# LED_Project.net
KiCad netlist of a schematic drawn in EAGLE
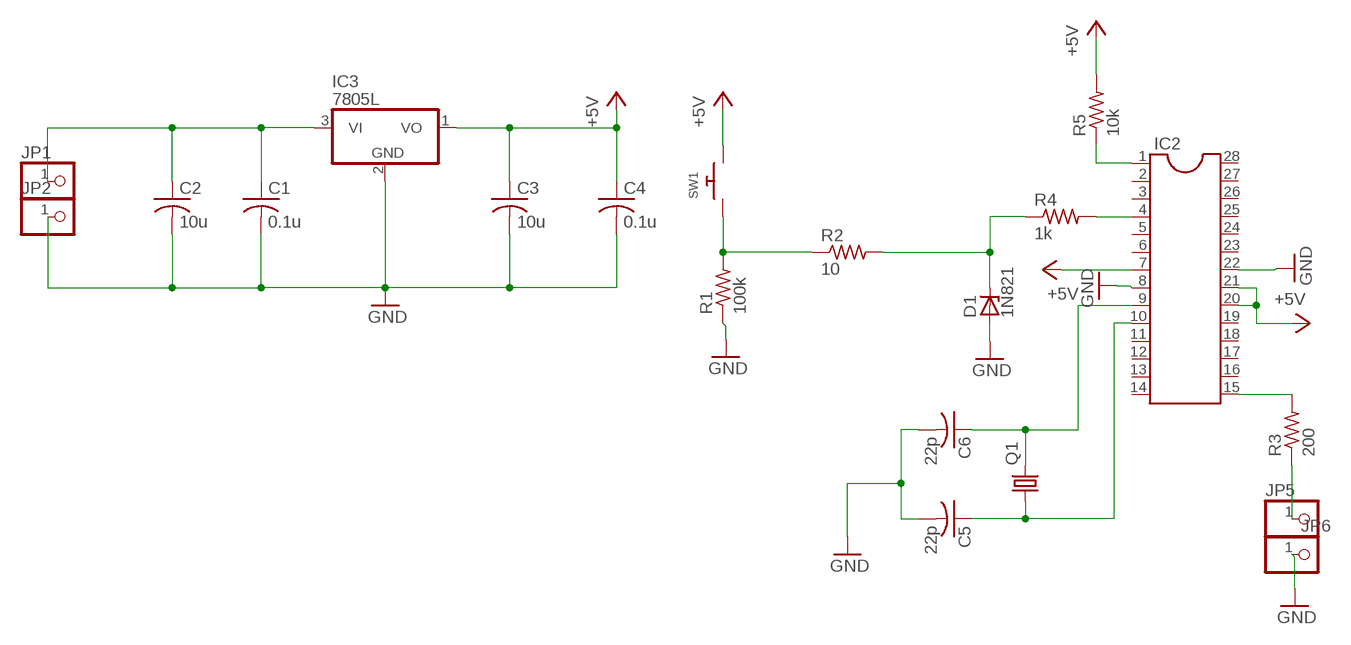
[diagram p0: schematic, sheet 1]

(export (version "E")
  (design (tool "Eeschema 10.0.6"))
  (components
    (comp (ref "C1")
      (value "0.1u")
      (footprint "eagle-import:C0805K")
      (libsource (lib "eagle-import") (part "C-USC0805K"))
    )
    (comp (ref "C2")
      (value "10u")
      (footprint "eagle-import:C0805K")
      (libsource (lib "eagle-import") (part "C-USC0805K"))
    )
    (comp (ref "C3")
      (value "10u")
      (footprint "eagle-import:C0805K")
      (libsource (lib "eagle-import") (part "C-USC0805K"))
    )
    (comp (ref "C4")
      (value "0.1u")
      (footprint "eagle-import:C0805K")
      (libsource (lib "eagle-import") (part "C-USC0805K"))
    )
    (comp (ref "C5")
      (value "22p")
      (footprint "eagle-import:C0805K")
      (libsource (lib "eagle-import") (part "C-USC0805K"))
    )
    (comp (ref "C6")
      (value "22p")
      (footprint "eagle-import:C0805K")
      (libsource (lib "eagle-import") (part "C-USC0805K"))
    )
    (comp (ref "D1")
      (value "1N821")
      (footprint "eagle-import:DO35Z10")
      (libsource (lib "eagle-import") (part "1N821"))
    )
    (comp (ref "IC2")
      (value "DIL28-3")
      (footprint "eagle-import:DIL28-3")
      (libsource (lib "eagle-import") (part "DIL28-3"))
    )
    (comp (ref "IC3")
      (value "7805L")
      (footprint "eagle-import:TO92")
      (libsource (lib "eagle-import") (part "78L05"))
    )
    (comp (ref "JP1")
      (value "PINHD-1X1")
      (footprint "eagle-import:1X01")
      (libsource (lib "eagle-import") (part "PINHD-1X1"))
    )
    (comp (ref "JP2")
      (value "PINHD-1X1")
      (footprint "eagle-import:1X01")
      (libsource (lib "eagle-import") (part "PINHD-1X1"))
    )
    (comp (ref "JP5")
      (value "PINHD-1X1")
      (footprint "eagle-import:1X01")
      (libsource (lib "eagle-import") (part "PINHD-1X1"))
    )
    (comp (ref "JP6")
      (value "PINHD-1X1")
      (footprint "eagle-import:1X01")
      (libsource (lib "eagle-import") (part "PINHD-1X1"))
    )
    (comp (ref "Q1")
      (value "CRYSTALHC49S")
      (footprint "eagle-import:HC49_S")
      (libsource (lib "eagle-import") (part "CRYSTALHC49S"))
    )
    (comp (ref "R1")
      (value "100k")
      (footprint "eagle-import:R0805")
      (libsource (lib "eagle-import") (part "R-US_R0805"))
    )
    (comp (ref "R2")
      (value "10")
      (footprint "eagle-import:R0805")
      (libsource (lib "eagle-import") (part "R-US_R0805"))
    )
    (comp (ref "R3")
      (value "200")
      (footprint "eagle-import:R0805")
      (libsource (lib "eagle-import") (part "R-US_R0805"))
    )
    (comp (ref "R4")
      (value "1k")
      (footprint "eagle-import:R0805")
      (libsource (lib "eagle-import") (part "R-US_R0805"))
    )
    (comp (ref "R5")
      (value "10k")
      (footprint "eagle-import:R0805")
      (libsource (lib "eagle-import") (part "R-US_R0805"))
    )
    (comp (ref "SW1")
      (value "SWITCH_PUSHBUTTONSOFTTOUCHSMD_SJ")
      (footprint "eagle-import:PUSHBUTTON_SMD_SJ")
      (libsource (lib "eagle-import") (part "SWITCH_PUSHBUTTONSOFTTOUCHSMD_SJ"))
    )
  )
  (nets
    (net (code "1") (name "+5V") (class "Default")
      (node (ref "C3") (pin "1") (pinfunction "1_1") (pintype "passive"))
      (node (ref "C4") (pin "1") (pinfunction "1_1") (pintype "passive"))
      (node (ref "IC2") (pin "20") (pinfunction "20_20") (pintype "passive"))
      (node (ref "IC2") (pin "21") (pinfunction "21_21") (pintype "passive"))
      (node (ref "IC2") (pin "7") (pinfunction "7_7") (pintype "passive"))
      (node (ref "IC3") (pin "1") (pinfunction "VO_1") (pintype "passive"))
      (node (ref "R5") (pin "2") (pinfunction "2_2") (pintype "passive"))
      (node (ref "SW1") (pin "P$2") (pinfunction "P$2_P$2") (pintype "passive"))
    )
    (net (code "2") (name "GND") (class "Default")
      (node (ref "C1") (pin "2") (pinfunction "2_2") (pintype "passive"))
      (node (ref "C2") (pin "2") (pinfunction "2_2") (pintype "passive"))
      (node (ref "C3") (pin "2") (pinfunction "2_2") (pintype "passive"))
      (node (ref "C4") (pin "2") (pinfunction "2_2") (pintype "passive"))
      (node (ref "C5") (pin "2") (pinfunction "2_2") (pintype "passive"))
      (node (ref "C6") (pin "2") (pinfunction "2_2") (pintype "passive"))
      (node (ref "D1") (pin "A") (pinfunction "A_A") (pintype "passive"))
      (node (ref "IC2") (pin "22") (pinfunction "22_22") (pintype "passive"))
      (node (ref "IC2") (pin "8") (pinfunction "8_8") (pintype "passive"))
      (node (ref "IC3") (pin "2") (pinfunction "GND_2") (pintype "passive"))
      (node (ref "JP2") (pin "1") (pinfunction "1_1") (pintype "passive"))
      (node (ref "JP6") (pin "1") (pinfunction "1_1") (pintype "passive"))
      (node (ref "R1") (pin "1") (pinfunction "1_1") (pintype "passive"))
    )
    (net (code "3") (name "Net-(C5-Pad1)") (class "Default")
      (node (ref "C5") (pin "1") (pinfunction "1_1") (pintype "passive"))
      (node (ref "IC2") (pin "10") (pinfunction "10_10") (pintype "passive"))
      (node (ref "Q1") (pin "1") (pinfunction "1_1") (pintype "passive"))
    )
    (net (code "4") (name "Net-(C6-Pad1)") (class "Default")
      (node (ref "C6") (pin "1") (pinfunction "1_1") (pintype "passive"))
      (node (ref "IC2") (pin "9") (pinfunction "9_9") (pintype "passive"))
      (node (ref "Q1") (pin "2") (pinfunction "2_2") (pintype "passive"))
    )
    (net (code "5") (name "Net-(D1-PadC)") (class "Default")
      (node (ref "D1") (pin "C") (pinfunction "C_C") (pintype "passive"))
      (node (ref "R2") (pin "2") (pinfunction "2_2") (pintype "passive"))
      (node (ref "R4") (pin "1") (pinfunction "1_1") (pintype "passive"))
    )
    (net (code "6") (name "Net-(IC2-Pad1)") (class "Default")
      (node (ref "IC2") (pin "1") (pinfunction "1_1") (pintype "passive"))
      (node (ref "R5") (pin "1") (pinfunction "1_1") (pintype "passive"))
    )
    (net (code "7") (name "Net-(IC2-Pad4)") (class "Default")
      (node (ref "IC2") (pin "4") (pinfunction "4_4") (pintype "passive"))
      (node (ref "R4") (pin "2") (pinfunction "2_2") (pintype "passive"))
    )
    (net (code "8") (name "Net-(IC2-Pad15)") (class "Default")
      (node (ref "IC2") (pin "15") (pinfunction "15_15") (pintype "passive"))
      (node (ref "R3") (pin "2") (pinfunction "2_2") (pintype "passive"))
    )
    (net (code "9") (name "Net-(IC3-VI)") (class "Default")
      (node (ref "C1") (pin "1") (pinfunction "1_1") (pintype "passive"))
      (node (ref "C2") (pin "1") (pinfunction "1_1") (pintype "passive"))
      (node (ref "IC3") (pin "3") (pinfunction "VI_3") (pintype "input"))
      (node (ref "JP1") (pin "1") (pinfunction "1_1") (pintype "passive"))
    )
    (net (code "10") (name "Net-(JP5-Pad1)") (class "Default")
      (node (ref "JP5") (pin "1") (pinfunction "1_1") (pintype "passive"))
      (node (ref "R3") (pin "1") (pinfunction "1_1") (pintype "passive"))
    )
    (net (code "11") (name "Net-(R1-Pad2)") (class "Default")
      (node (ref "R1") (pin "2") (pinfunction "2_2") (pintype "passive"))
      (node (ref "R2") (pin "1") (pinfunction "1_1") (pintype "passive"))
      (node (ref "SW1") (pin "P$1") (pinfunction "P$1_P$1") (pintype "passive"))
    )
    (net (code "12") (name "unconnected-(IC2-Pad2)") (class "Default")
      (node (ref "IC2") (pin "2") (pinfunction "2_2") (pintype "passive"))
    )
    (net (code "13") (name "unconnected-(IC2-Pad3)") (class "Default")
      (node (ref "IC2") (pin "3") (pinfunction "3_3") (pintype "passive"))
    )
    (net (code "14") (name "unconnected-(IC2-Pad5)") (class "Default")
      (node (ref "IC2") (pin "5") (pinfunction "5_5") (pintype "passive"))
    )
    (net (code "15") (name "unconnected-(IC2-Pad6)") (class "Default")
      (node (ref "IC2") (pin "6") (pinfunction "6_6") (pintype "passive"))
    )
    (net (code "16") (name "unconnected-(IC2-Pad11)") (class "Default")
      (node (ref "IC2") (pin "11") (pinfunction "11_11") (pintype "passive"))
    )
    (net (code "17") (name "unconnected-(IC2-Pad12)") (class "Default")
      (node (ref "IC2") (pin "12") (pinfunction "12_12") (pintype "passive"))
    )
    (net (code "18") (name "unconnected-(IC2-Pad13)") (class "Default")
      (node (ref "IC2") (pin "13") (pinfunction "13_13") (pintype "passive"))
    )
    (net (code "19") (name "unconnected-(IC2-Pad14)") (class "Default")
      (node (ref "IC2") (pin "14") (pinfunction "14_14") (pintype "passive"))
    )
    (net (code "20") (name "unconnected-(IC2-Pad16)") (class "Default")
      (node (ref "IC2") (pin "16") (pinfunction "16_16") (pintype "passive"))
    )
    (net (code "21") (name "unconnected-(IC2-Pad17)") (class "Default")
      (node (ref "IC2") (pin "17") (pinfunction "17_17") (pintype "passive"))
    )
    (net (code "22") (name "unconnected-(IC2-Pad18)") (class "Default")
      (node (ref "IC2") (pin "18") (pinfunction "18_18") (pintype "passive"))
    )
    (net (code "23") (name "unconnected-(IC2-Pad19)") (class "Default")
      (node (ref "IC2") (pin "19") (pinfunction "19_19") (pintype "passive"))
    )
    (net (code "24") (name "unconnected-(IC2-Pad23)") (class "Default")
      (node (ref "IC2") (pin "23") (pinfunction "23_23") (pintype "passive"))
    )
    (net (code "25") (name "unconnected-(IC2-Pad24)") (class "Default")
      (node (ref "IC2") (pin "24") (pinfunction "24_24") (pintype "passive"))
    )
    (net (code "26") (name "unconnected-(IC2-Pad25)") (class "Default")
      (node (ref "IC2") (pin "25") (pinfunction "25_25") (pintype "passive"))
    )
    (net (code "27") (name "unconnected-(IC2-Pad26)") (class "Default")
      (node (ref "IC2") (pin "26") (pinfunction "26_26") (pintype "passive"))
    )
    (net (code "28") (name "unconnected-(IC2-Pad27)") (class "Default")
      (node (ref "IC2") (pin "27") (pinfunction "27_27") (pintype "passive"))
    )
    (net (code "29") (name "unconnected-(IC2-Pad28)") (class "Default")
      (node (ref "IC2") (pin "28") (pinfunction "28_28") (pintype "passive"))
    )
  )
)
